# Gadget-Box-NodeMCU.net
KiCad netlist of a schematic drawn in EAGLE
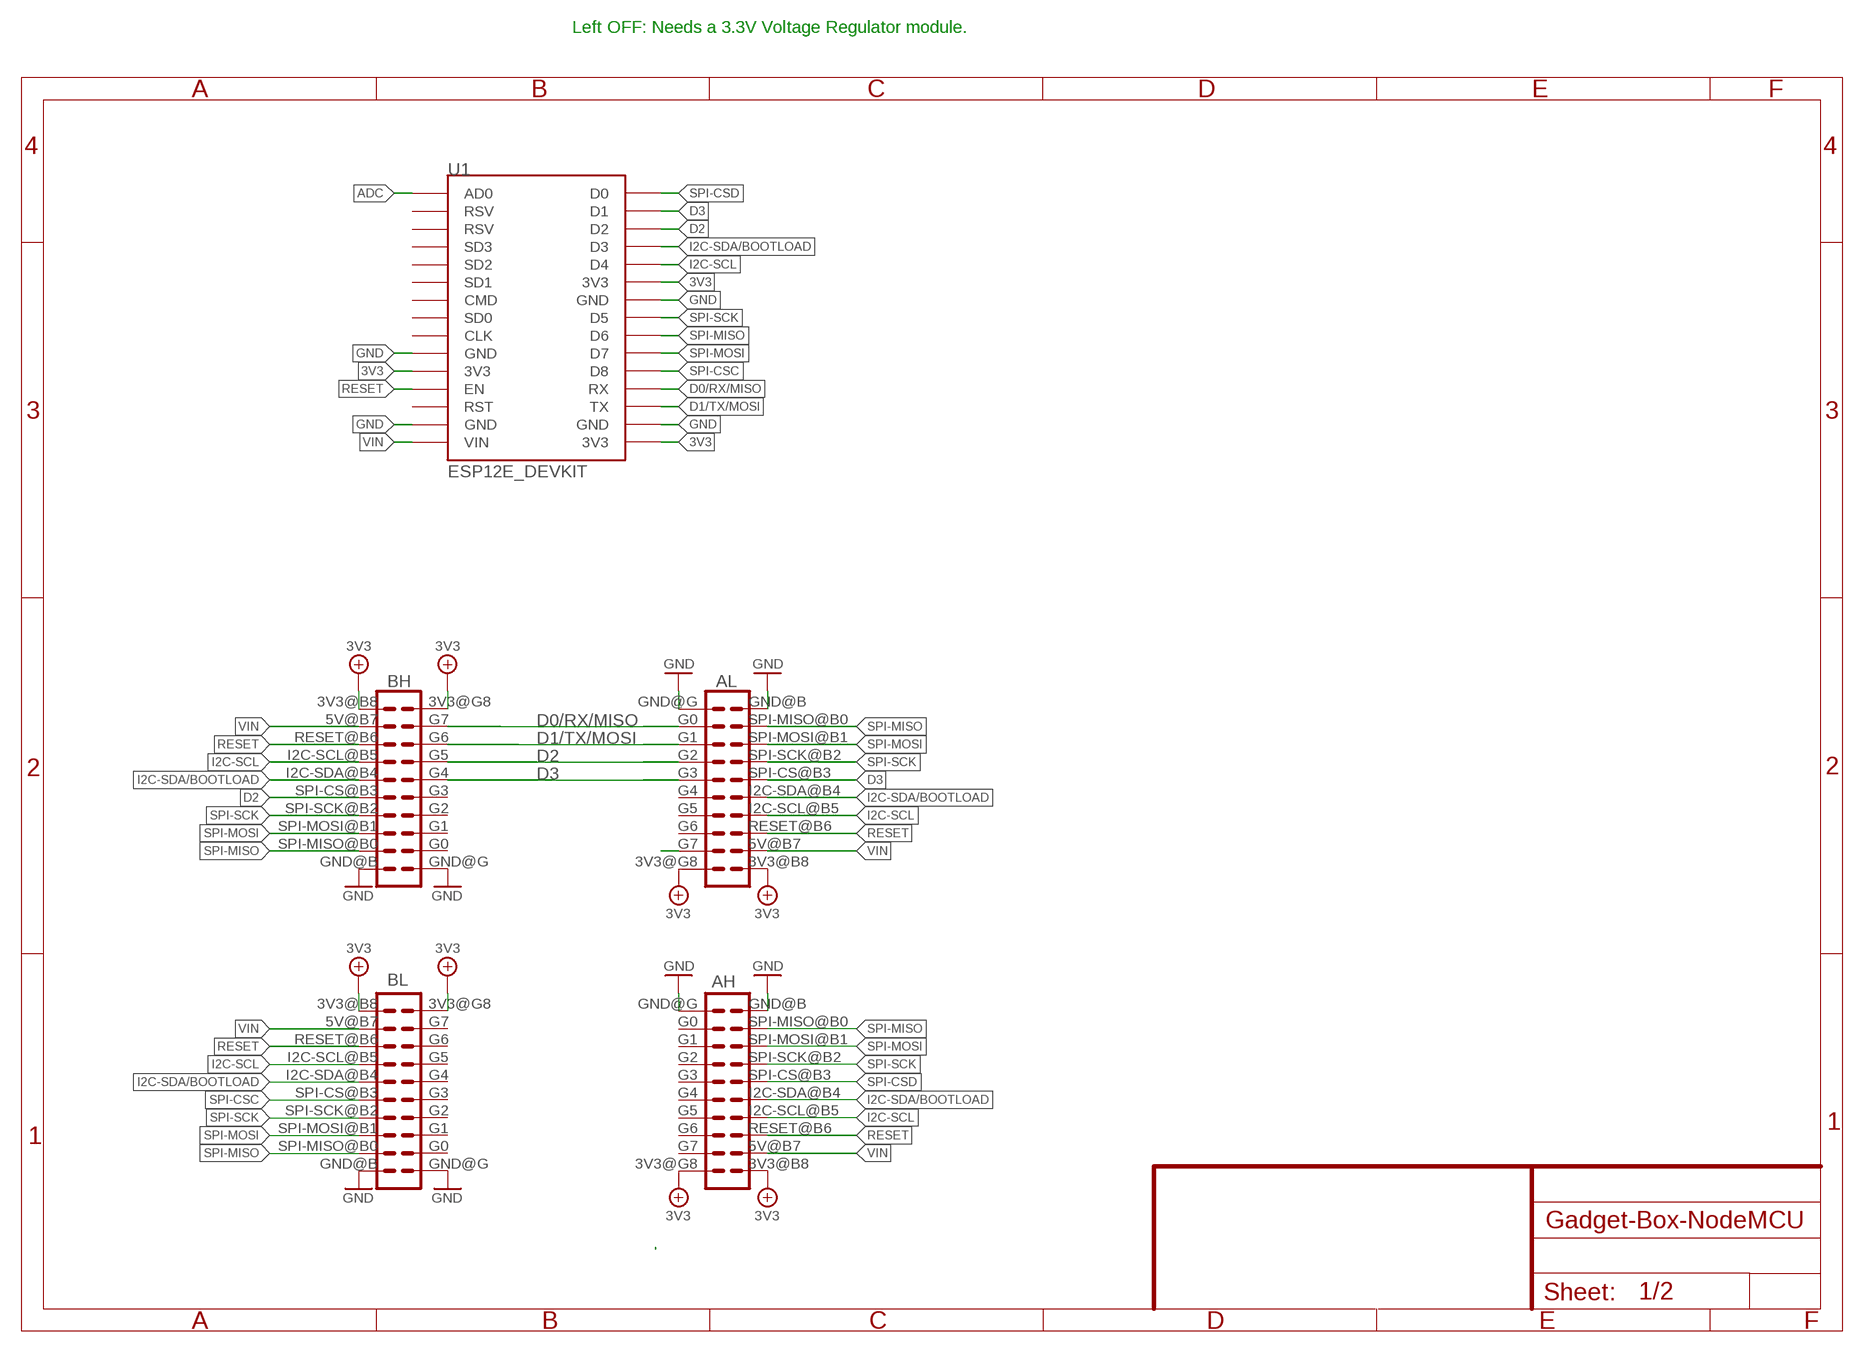
[diagram p0: schematic, sheet 1]
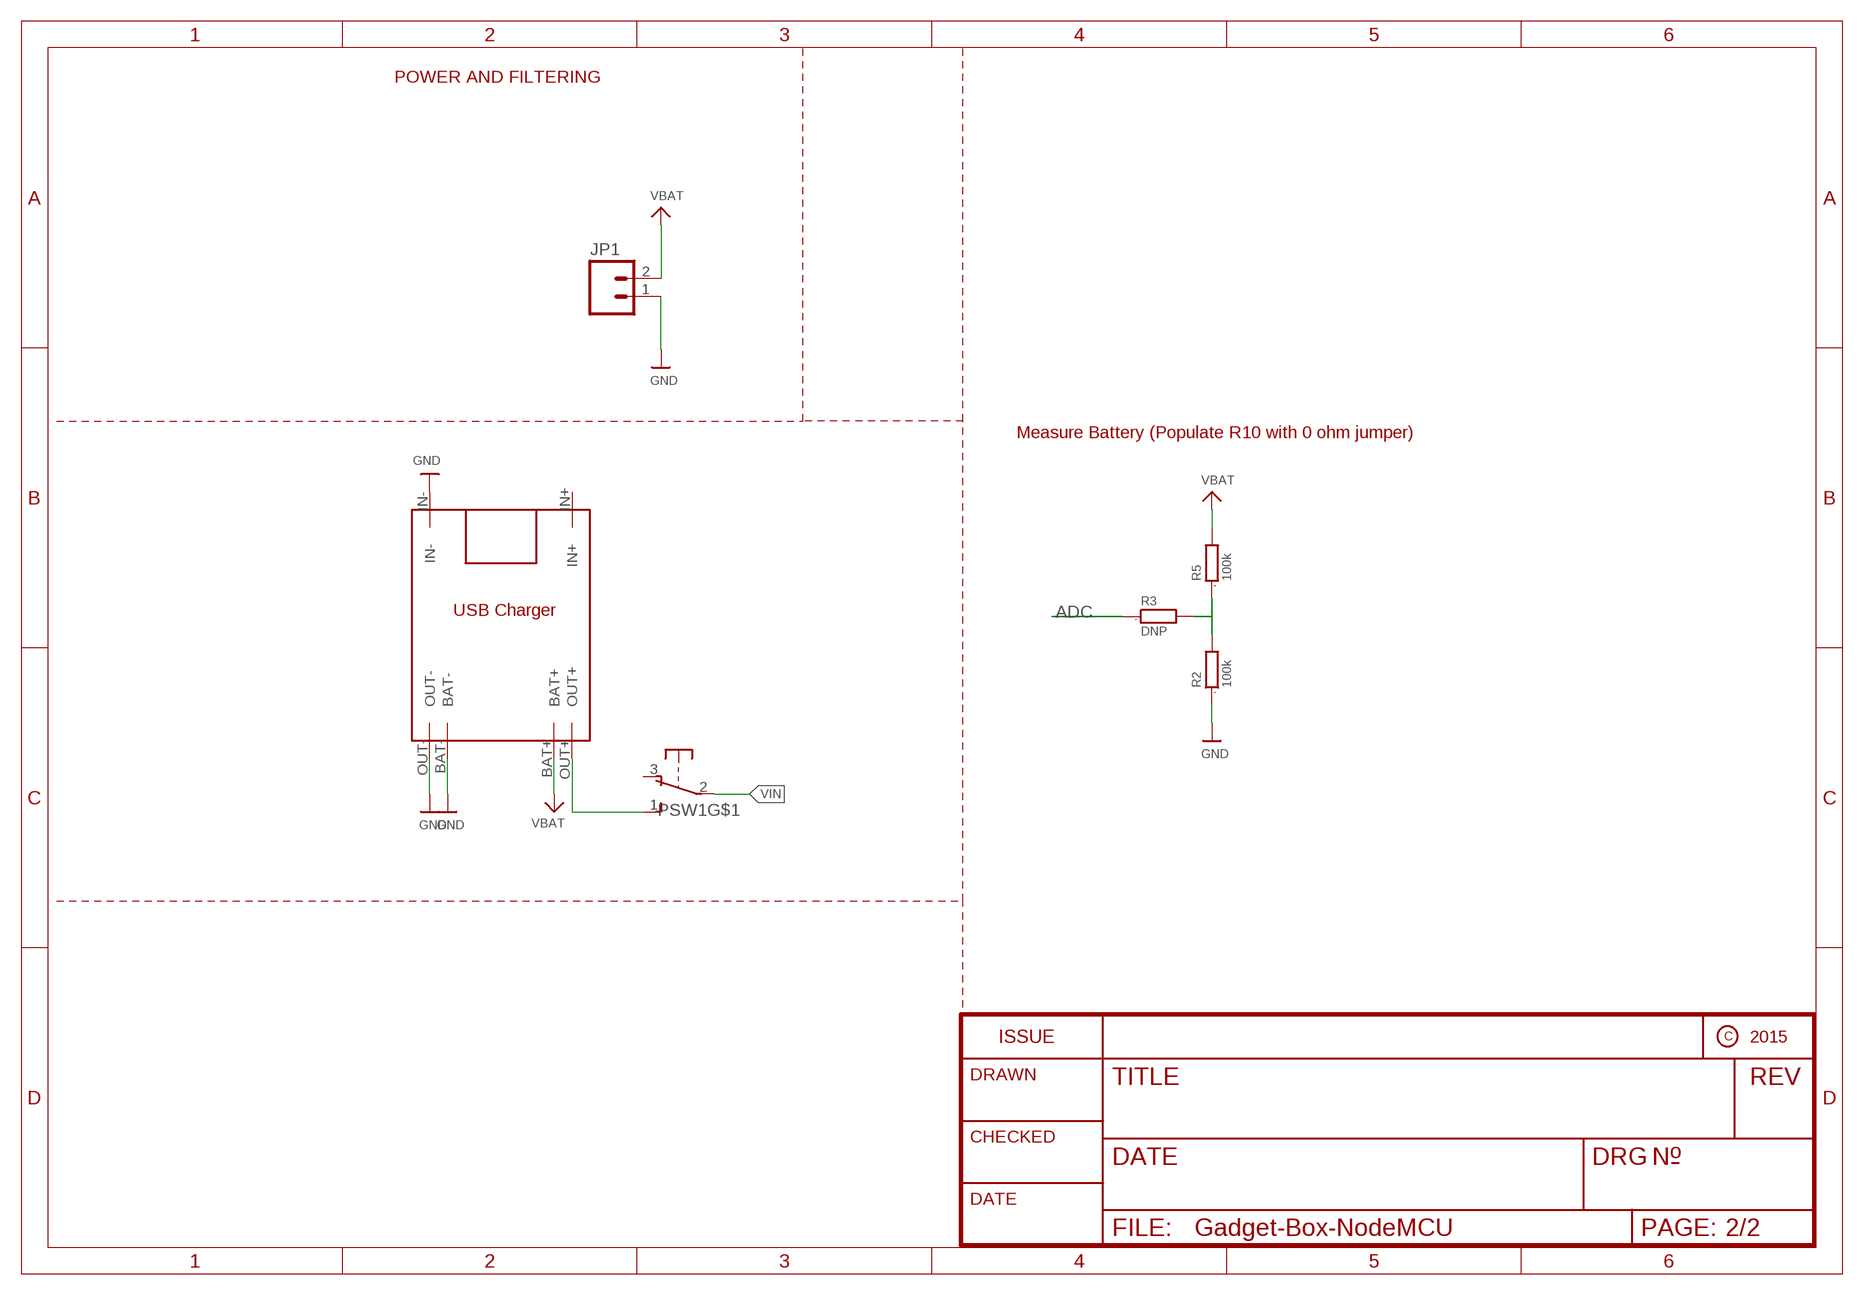
[diagram p1: schematic, sheet 2]

(export (version "E")
  (design (tool "Eeschema 10.0.6"))
  (components
    (comp (ref "JP1")
      (value "M02-JST-2-PTH-NO_SILK")
      (footprint "eagle-import:JST-2-PTH-NS")
      (libsource (lib "eagle-import") (part "M02-JST-2-PTH-NO_SILK"))
    )
    (comp (ref "PSW1")
      (value "OS102011MA1Q")
      (footprint "eagle-import:OS102011MA1Q")
      (fields
        (field (name "PARTNO") "OS102011MA1QN1,C&K Components,dk,CKN9559-ND,SWITCH SLIDE SPDT 100MA 12V , REF72")
      )
      (libsource (lib "eagle-import") (part "OS102011MA1Q"))
    )
    (comp (ref "R2")
      (value "100k")
      (footprint "eagle-import:0603")
      (fields
        (field (name "PARTNO") "RC0603JR-07100KL,YAGEO (VA),dk,311-100KGRCT-ND,RES SMD 100K OHM 5% 1/10W 0603 , REF76")
      )
      (libsource (lib "eagle-import") (part "R0603"))
    )
    (comp (ref "R3")
      (value "DNP")
      (footprint "eagle-import:0603")
      (libsource (lib "eagle-import") (part "R0603"))
    )
    (comp (ref "R5")
      (value "100k")
      (footprint "eagle-import:0603")
      (fields
        (field (name "PARTNO") "RC0603JR-07100KL,YAGEO (VA),dk,311-100KGRCT-ND,RES SMD 100K OHM 5% 1/10W 0603 , REF76")
      )
      (libsource (lib "eagle-import") (part "R0603"))
    )
    (comp (ref "U$1")
      (value "TP4056")
      (footprint "eagle-import:TP4056")
      (libsource (lib "eagle-import") (part "TP4056"))
    )
    (comp (ref "AH")
      (value "ECOGECOG_SLOT")
      (footprint "eagle-import:ECOG")
      (libsource (lib "eagle-import") (part "ECOGECOG_SLOT"))
    )
    (comp (ref "AL")
      (value "ECOGECOG_SLOT")
      (footprint "eagle-import:ECOG")
      (libsource (lib "eagle-import") (part "ECOGECOG_SLOT"))
    )
    (comp (ref "BH")
      (value "ECOGECOG_SLOT")
      (footprint "eagle-import:ECOG")
      (libsource (lib "eagle-import") (part "ECOGECOG_SLOT"))
    )
    (comp (ref "BL")
      (value "ECOGECOG_SLOT")
      (footprint "eagle-import:ECOG")
      (libsource (lib "eagle-import") (part "ECOGECOG_SLOT"))
    )
    (comp (ref "U1")
      (value "ESP12E_DEVKIT")
      (footprint "eagle-import:ESP12E_DEVKIT")
      (libsource (lib "eagle-import") (part "ESP12E_DEVKIT"))
    )
  )
  (nets
    (net (code "1") (name "3V3") (class "Default")
      (node (ref "AH") (pin "3V3@B8") (pinfunction "3V3_3V3@B8") (pintype "passive"))
      (node (ref "AH") (pin "3V3@G8") (pinfunction "3V3_3V3@G8") (pintype "passive"))
      (node (ref "AL") (pin "3V3@B8") (pinfunction "3V3_3V3@B8") (pintype "passive"))
      (node (ref "AL") (pin "3V3@G8") (pinfunction "3V3_3V3@G8") (pintype "passive"))
      (node (ref "BH") (pin "3V3@B8") (pinfunction "3V3_3V3@B8") (pintype "passive"))
      (node (ref "BH") (pin "3V3@G8") (pinfunction "3V3_3V3@G8") (pintype "passive"))
      (node (ref "BL") (pin "3V3@B8") (pinfunction "3V3_3V3@B8") (pintype "passive"))
      (node (ref "BL") (pin "3V3@G8") (pinfunction "3V3_3V3@G8") (pintype "passive"))
      (node (ref "U1") (pin "3V3@0") (pinfunction "3V3_3V3@0") (pintype "bidirectional"))
      (node (ref "U1") (pin "3V3@1") (pinfunction "3V3_3V3@1") (pintype "bidirectional"))
      (node (ref "U1") (pin "3V3@2") (pinfunction "3V3_3V3@2") (pintype "bidirectional"))
    )
    (net (code "2") (name "ADC") (class "Default")
      (node (ref "R3") (pin "1") (pinfunction "1_1") (pintype "passive"))
      (node (ref "U1") (pin "AD0") (pinfunction "AD0_AD0") (pintype "bidirectional"))
    )
    (net (code "3") (name "D0{slash}RX{slash}MISO") (class "Default")
      (node (ref "AL") (pin "G0") (pinfunction "G0_G0") (pintype "passive"))
      (node (ref "BH") (pin "G7") (pinfunction "G7_G7") (pintype "passive"))
      (node (ref "U1") (pin "RX") (pinfunction "RX_RX") (pintype "bidirectional"))
    )
    (net (code "4") (name "D1{slash}TX{slash}MOSI") (class "Default")
      (node (ref "AL") (pin "G1") (pinfunction "G1_G1") (pintype "passive"))
      (node (ref "BH") (pin "G6") (pinfunction "G6_G6") (pintype "passive"))
      (node (ref "U1") (pin "TX") (pinfunction "TX_TX") (pintype "bidirectional"))
    )
    (net (code "5") (name "D2") (class "Default")
      (node (ref "AL") (pin "G2") (pinfunction "G2_G2") (pintype "passive"))
      (node (ref "BH") (pin "G5") (pinfunction "G5_G5") (pintype "passive"))
      (node (ref "BH") (pin "SPI-CS@B3") (pinfunction "SPI-CS_SPI-CS@B3") (pintype "passive"))
      (node (ref "U1") (pin "D2") (pinfunction "D2_D2") (pintype "bidirectional"))
    )
    (net (code "6") (name "D3") (class "Default")
      (node (ref "AL") (pin "G3") (pinfunction "G3_G3") (pintype "passive"))
      (node (ref "AL") (pin "SPI-CS@B3") (pinfunction "SPI-CS_SPI-CS@B3") (pintype "passive"))
      (node (ref "BH") (pin "G4") (pinfunction "G4_G4") (pintype "passive"))
      (node (ref "U1") (pin "D1") (pinfunction "D1_D1") (pintype "bidirectional"))
    )
    (net (code "7") (name "GND") (class "Default")
      (node (ref "AH") (pin "GND@B") (pinfunction "GND_GND@B") (pintype "passive"))
      (node (ref "AH") (pin "GND@G") (pinfunction "GND_GND@G") (pintype "passive"))
      (node (ref "AL") (pin "GND@B") (pinfunction "GND_GND@B") (pintype "passive"))
      (node (ref "AL") (pin "GND@G") (pinfunction "GND_GND@G") (pintype "passive"))
      (node (ref "BH") (pin "GND@B") (pinfunction "GND_GND@B") (pintype "passive"))
      (node (ref "BH") (pin "GND@G") (pinfunction "GND_GND@G") (pintype "passive"))
      (node (ref "BL") (pin "GND@B") (pinfunction "GND_GND@B") (pintype "passive"))
      (node (ref "BL") (pin "GND@G") (pinfunction "GND_GND@G") (pintype "passive"))
      (node (ref "JP1") (pin "1") (pinfunction "1_1") (pintype "passive"))
      (node (ref "R2") (pin "1") (pinfunction "1_1") (pintype "passive"))
      (node (ref "U$1") (pin "BAT-") (pinfunction "BAT-_BAT-") (pintype "bidirectional"))
      (node (ref "U$1") (pin "IN-") (pinfunction "IN-_IN-") (pintype "bidirectional"))
      (node (ref "U$1") (pin "OUT-") (pinfunction "OUT-_OUT-") (pintype "bidirectional"))
      (node (ref "U1") (pin "GND@0") (pinfunction "GND_GND@0") (pintype "bidirectional"))
      (node (ref "U1") (pin "GND@1") (pinfunction "GND_GND@1") (pintype "bidirectional"))
      (node (ref "U1") (pin "GND@2") (pinfunction "GND_GND@2") (pintype "bidirectional"))
      (node (ref "U1") (pin "GND@3") (pinfunction "GND_GND@3") (pintype "bidirectional"))
    )
    (net (code "8") (name "I2C-SCL") (class "Default")
      (node (ref "AH") (pin "I2C-SCL@B5") (pinfunction "I2C-SCL_I2C-SCL@B5") (pintype "passive"))
      (node (ref "AL") (pin "I2C-SCL@B5") (pinfunction "I2C-SCL_I2C-SCL@B5") (pintype "passive"))
      (node (ref "BH") (pin "I2C-SCL@B5") (pinfunction "I2C-SCL_I2C-SCL@B5") (pintype "passive"))
      (node (ref "BL") (pin "I2C-SCL@B5") (pinfunction "I2C-SCL_I2C-SCL@B5") (pintype "passive"))
      (node (ref "U1") (pin "D4") (pinfunction "D4_D4") (pintype "bidirectional"))
    )
    (net (code "9") (name "I2C-SDA{slash}BOOTLOAD") (class "Default")
      (node (ref "AH") (pin "I2C-SDA@B4") (pinfunction "I2C-SDA_I2C-SDA@B4") (pintype "passive"))
      (node (ref "AL") (pin "I2C-SDA@B4") (pinfunction "I2C-SDA_I2C-SDA@B4") (pintype "passive"))
      (node (ref "BH") (pin "I2C-SDA@B4") (pinfunction "I2C-SDA_I2C-SDA@B4") (pintype "passive"))
      (node (ref "BL") (pin "I2C-SDA@B4") (pinfunction "I2C-SDA_I2C-SDA@B4") (pintype "passive"))
      (node (ref "U1") (pin "D3") (pinfunction "D3_D3") (pintype "bidirectional"))
    )
    (net (code "10") (name "Net-(PSW1A-S)") (class "Default")
      (node (ref "PSW1") (pin "1") (pinfunction "S_1") (pintype "passive"))
      (node (ref "U$1") (pin "OUT+") (pinfunction "OUT+_OUT+") (pintype "bidirectional"))
    )
    (net (code "11") (name "Net-(R2-Pad2)") (class "Default")
      (node (ref "R2") (pin "2") (pinfunction "2_2") (pintype "passive"))
      (node (ref "R3") (pin "2") (pinfunction "2_2") (pintype "passive"))
      (node (ref "R5") (pin "1") (pinfunction "1_1") (pintype "passive"))
    )
    (net (code "12") (name "RESET") (class "Default")
      (node (ref "AH") (pin "RESET@B6") (pinfunction "RESET_RESET@B6") (pintype "passive"))
      (node (ref "AL") (pin "RESET@B6") (pinfunction "RESET_RESET@B6") (pintype "passive"))
      (node (ref "BH") (pin "RESET@B6") (pinfunction "RESET_RESET@B6") (pintype "passive"))
      (node (ref "BL") (pin "RESET@B6") (pinfunction "RESET_RESET@B6") (pintype "passive"))
      (node (ref "U1") (pin "EN") (pinfunction "EN_EN") (pintype "bidirectional"))
    )
    (net (code "13") (name "SPI-CSC") (class "Default")
      (node (ref "BL") (pin "SPI-CS@B3") (pinfunction "SPI-CS_SPI-CS@B3") (pintype "passive"))
      (node (ref "U1") (pin "D8") (pinfunction "D8_D8") (pintype "bidirectional"))
    )
    (net (code "14") (name "SPI-CSD") (class "Default")
      (node (ref "AH") (pin "SPI-CS@B3") (pinfunction "SPI-CS_SPI-CS@B3") (pintype "passive"))
      (node (ref "U1") (pin "D0") (pinfunction "D0_D0") (pintype "bidirectional"))
    )
    (net (code "15") (name "SPI-MISO") (class "Default")
      (node (ref "AH") (pin "SPI-MISO@B0") (pinfunction "SPI-MISO_SPI-MISO@B0") (pintype "passive"))
      (node (ref "AL") (pin "SPI-MISO@B0") (pinfunction "SPI-MISO_SPI-MISO@B0") (pintype "passive"))
      (node (ref "BH") (pin "SPI-MISO@B0") (pinfunction "SPI-MISO_SPI-MISO@B0") (pintype "passive"))
      (node (ref "BL") (pin "SPI-MISO@B0") (pinfunction "SPI-MISO_SPI-MISO@B0") (pintype "passive"))
      (node (ref "U1") (pin "D6") (pinfunction "D6_D6") (pintype "bidirectional"))
    )
    (net (code "16") (name "SPI-MOSI") (class "Default")
      (node (ref "AH") (pin "SPI-MOSI@B1") (pinfunction "SPI-MOSI_SPI-MOSI@B1") (pintype "passive"))
      (node (ref "AL") (pin "SPI-MOSI@B1") (pinfunction "SPI-MOSI_SPI-MOSI@B1") (pintype "passive"))
      (node (ref "BH") (pin "SPI-MOSI@B1") (pinfunction "SPI-MOSI_SPI-MOSI@B1") (pintype "passive"))
      (node (ref "BL") (pin "SPI-MOSI@B1") (pinfunction "SPI-MOSI_SPI-MOSI@B1") (pintype "passive"))
      (node (ref "U1") (pin "D7") (pinfunction "D7_D7") (pintype "bidirectional"))
    )
    (net (code "17") (name "SPI-SCK") (class "Default")
      (node (ref "AH") (pin "SPI-SCK@B2") (pinfunction "SPI-SCK_SPI-SCK@B2") (pintype "passive"))
      (node (ref "AL") (pin "SPI-SCK@B2") (pinfunction "SPI-SCK_SPI-SCK@B2") (pintype "passive"))
      (node (ref "BH") (pin "SPI-SCK@B2") (pinfunction "SPI-SCK_SPI-SCK@B2") (pintype "passive"))
      (node (ref "BL") (pin "SPI-SCK@B2") (pinfunction "SPI-SCK_SPI-SCK@B2") (pintype "passive"))
      (node (ref "U1") (pin "D5") (pinfunction "D5_D5") (pintype "bidirectional"))
    )
    (net (code "18") (name "VBAT") (class "Default")
      (node (ref "JP1") (pin "2") (pinfunction "2_2") (pintype "passive"))
      (node (ref "R5") (pin "2") (pinfunction "2_2") (pintype "passive"))
      (node (ref "U$1") (pin "BAT+") (pinfunction "BAT+_BAT+") (pintype "bidirectional"))
    )
    (net (code "19") (name "VIN") (class "Default")
      (node (ref "AH") (pin "5V@B7") (pinfunction "5V_5V@B7") (pintype "passive"))
      (node (ref "AL") (pin "5V@B7") (pinfunction "5V_5V@B7") (pintype "passive"))
      (node (ref "BH") (pin "5V@B7") (pinfunction "5V_5V@B7") (pintype "passive"))
      (node (ref "BL") (pin "5V@B7") (pinfunction "5V_5V@B7") (pintype "passive"))
      (node (ref "PSW1") (pin "2") (pinfunction "P_2") (pintype "passive"))
      (node (ref "U1") (pin "VIN") (pinfunction "VIN_VIN") (pintype "bidirectional"))
    )
    (net (code "20") (name "unconnected-(AH-PadG0)") (class "Default")
      (node (ref "AH") (pin "G0") (pinfunction "G0_G0") (pintype "passive"))
    )
    (net (code "21") (name "unconnected-(AH-PadG1)") (class "Default")
      (node (ref "AH") (pin "G1") (pinfunction "G1_G1") (pintype "passive"))
    )
    (net (code "22") (name "unconnected-(AH-PadG2)") (class "Default")
      (node (ref "AH") (pin "G2") (pinfunction "G2_G2") (pintype "passive"))
    )
    (net (code "23") (name "unconnected-(AH-PadG3)") (class "Default")
      (node (ref "AH") (pin "G3") (pinfunction "G3_G3") (pintype "passive"))
    )
    (net (code "24") (name "unconnected-(AH-PadG4)") (class "Default")
      (node (ref "AH") (pin "G4") (pinfunction "G4_G4") (pintype "passive"))
    )
    (net (code "25") (name "unconnected-(AH-PadG5)") (class "Default")
      (node (ref "AH") (pin "G5") (pinfunction "G5_G5") (pintype "passive"))
    )
    (net (code "26") (name "unconnected-(AH-PadG6)") (class "Default")
      (node (ref "AH") (pin "G6") (pinfunction "G6_G6") (pintype "passive"))
    )
    (net (code "27") (name "unconnected-(AH-PadG7)") (class "Default")
      (node (ref "AH") (pin "G7") (pinfunction "G7_G7") (pintype "passive"))
    )
    (net (code "28") (name "unconnected-(AL-PadG4)") (class "Default")
      (node (ref "AL") (pin "G4") (pinfunction "G4_G4") (pintype "passive"))
    )
    (net (code "29") (name "unconnected-(AL-PadG5)") (class "Default")
      (node (ref "AL") (pin "G5") (pinfunction "G5_G5") (pintype "passive"))
    )
    (net (code "30") (name "unconnected-(AL-PadG6)") (class "Default")
      (node (ref "AL") (pin "G6") (pinfunction "G6_G6") (pintype "passive"))
    )
    (net (code "31") (name "unconnected-(AL-PadG7)") (class "Default")
      (node (ref "AL") (pin "G7") (pinfunction "G7_G7") (pintype "passive"))
    )
    (net (code "32") (name "unconnected-(BH-PadG0)") (class "Default")
      (node (ref "BH") (pin "G0") (pinfunction "G0_G0") (pintype "passive"))
    )
    (net (code "33") (name "unconnected-(BH-PadG1)") (class "Default")
      (node (ref "BH") (pin "G1") (pinfunction "G1_G1") (pintype "passive"))
    )
    (net (code "34") (name "unconnected-(BH-PadG2)") (class "Default")
      (node (ref "BH") (pin "G2") (pinfunction "G2_G2") (pintype "passive"))
    )
    (net (code "35") (name "unconnected-(BH-PadG3)") (class "Default")
      (node (ref "BH") (pin "G3") (pinfunction "G3_G3") (pintype "passive"))
    )
    (net (code "36") (name "unconnected-(BL-PadG0)") (class "Default")
      (node (ref "BL") (pin "G0") (pinfunction "G0_G0") (pintype "passive"))
    )
    (net (code "37") (name "unconnected-(BL-PadG1)") (class "Default")
      (node (ref "BL") (pin "G1") (pinfunction "G1_G1") (pintype "passive"))
    )
    (net (code "38") (name "unconnected-(BL-PadG2)") (class "Default")
      (node (ref "BL") (pin "G2") (pinfunction "G2_G2") (pintype "passive"))
    )
    (net (code "39") (name "unconnected-(BL-PadG3)") (class "Default")
      (node (ref "BL") (pin "G3") (pinfunction "G3_G3") (pintype "passive"))
    )
    (net (code "40") (name "unconnected-(BL-PadG4)") (class "Default")
      (node (ref "BL") (pin "G4") (pinfunction "G4_G4") (pintype "passive"))
    )
    (net (code "41") (name "unconnected-(BL-PadG5)") (class "Default")
      (node (ref "BL") (pin "G5") (pinfunction "G5_G5") (pintype "passive"))
    )
    (net (code "42") (name "unconnected-(BL-PadG6)") (class "Default")
      (node (ref "BL") (pin "G6") (pinfunction "G6_G6") (pintype "passive"))
    )
    (net (code "43") (name "unconnected-(BL-PadG7)") (class "Default")
      (node (ref "BL") (pin "G7") (pinfunction "G7_G7") (pintype "passive"))
    )
    (net (code "44") (name "unconnected-(PSW1A-O-Pad3)") (class "Default")
      (node (ref "PSW1") (pin "3") (pinfunction "O_3") (pintype "passive"))
    )
    (net (code "45") (name "unconnected-(U$1-PadIN+)") (class "Default")
      (node (ref "U$1") (pin "IN+") (pinfunction "IN+_IN+") (pintype "bidirectional"))
    )
    (net (code "46") (name "unconnected-(U1-PadCLK)") (class "Default")
      (node (ref "U1") (pin "CLK") (pinfunction "CLK_CLK") (pintype "bidirectional"))
    )
    (net (code "47") (name "unconnected-(U1-PadCMD)") (class "Default")
      (node (ref "U1") (pin "CMD") (pinfunction "CMD_CMD") (pintype "bidirectional"))
    )
    (net (code "48") (name "unconnected-(U1-PadRST)") (class "Default")
      (node (ref "U1") (pin "RST") (pinfunction "RST_RST") (pintype "bidirectional"))
    )
    (net (code "49") (name "unconnected-(U1-PadSD0)") (class "Default")
      (node (ref "U1") (pin "SD0") (pinfunction "SD0_SD0") (pintype "bidirectional"))
    )
    (net (code "50") (name "unconnected-(U1-PadSD1)") (class "Default")
      (node (ref "U1") (pin "SD1") (pinfunction "SD1_SD1") (pintype "bidirectional"))
    )
    (net (code "51") (name "unconnected-(U1-PadSD2)") (class "Default")
      (node (ref "U1") (pin "SD2") (pinfunction "SD2_SD2") (pintype "bidirectional"))
    )
    (net (code "52") (name "unconnected-(U1-PadSD3)") (class "Default")
      (node (ref "U1") (pin "SD3") (pinfunction "SD3_SD3") (pintype "bidirectional"))
    )
    (net (code "53") (name "unconnected-(U1-RSV-PadRSV@0)") (class "Default")
      (node (ref "U1") (pin "RSV@0") (pinfunction "RSV_RSV@0") (pintype "bidirectional"))
    )
    (net (code "54") (name "unconnected-(U1-RSV-PadRSV@1)") (class "Default")
      (node (ref "U1") (pin "RSV@1") (pinfunction "RSV_RSV@1") (pintype "bidirectional"))
    )
  )
)
